# MCU099_02_XDS110_Debug_Probe.net
KiCad netlist of a schematic drawn in Altium Designer
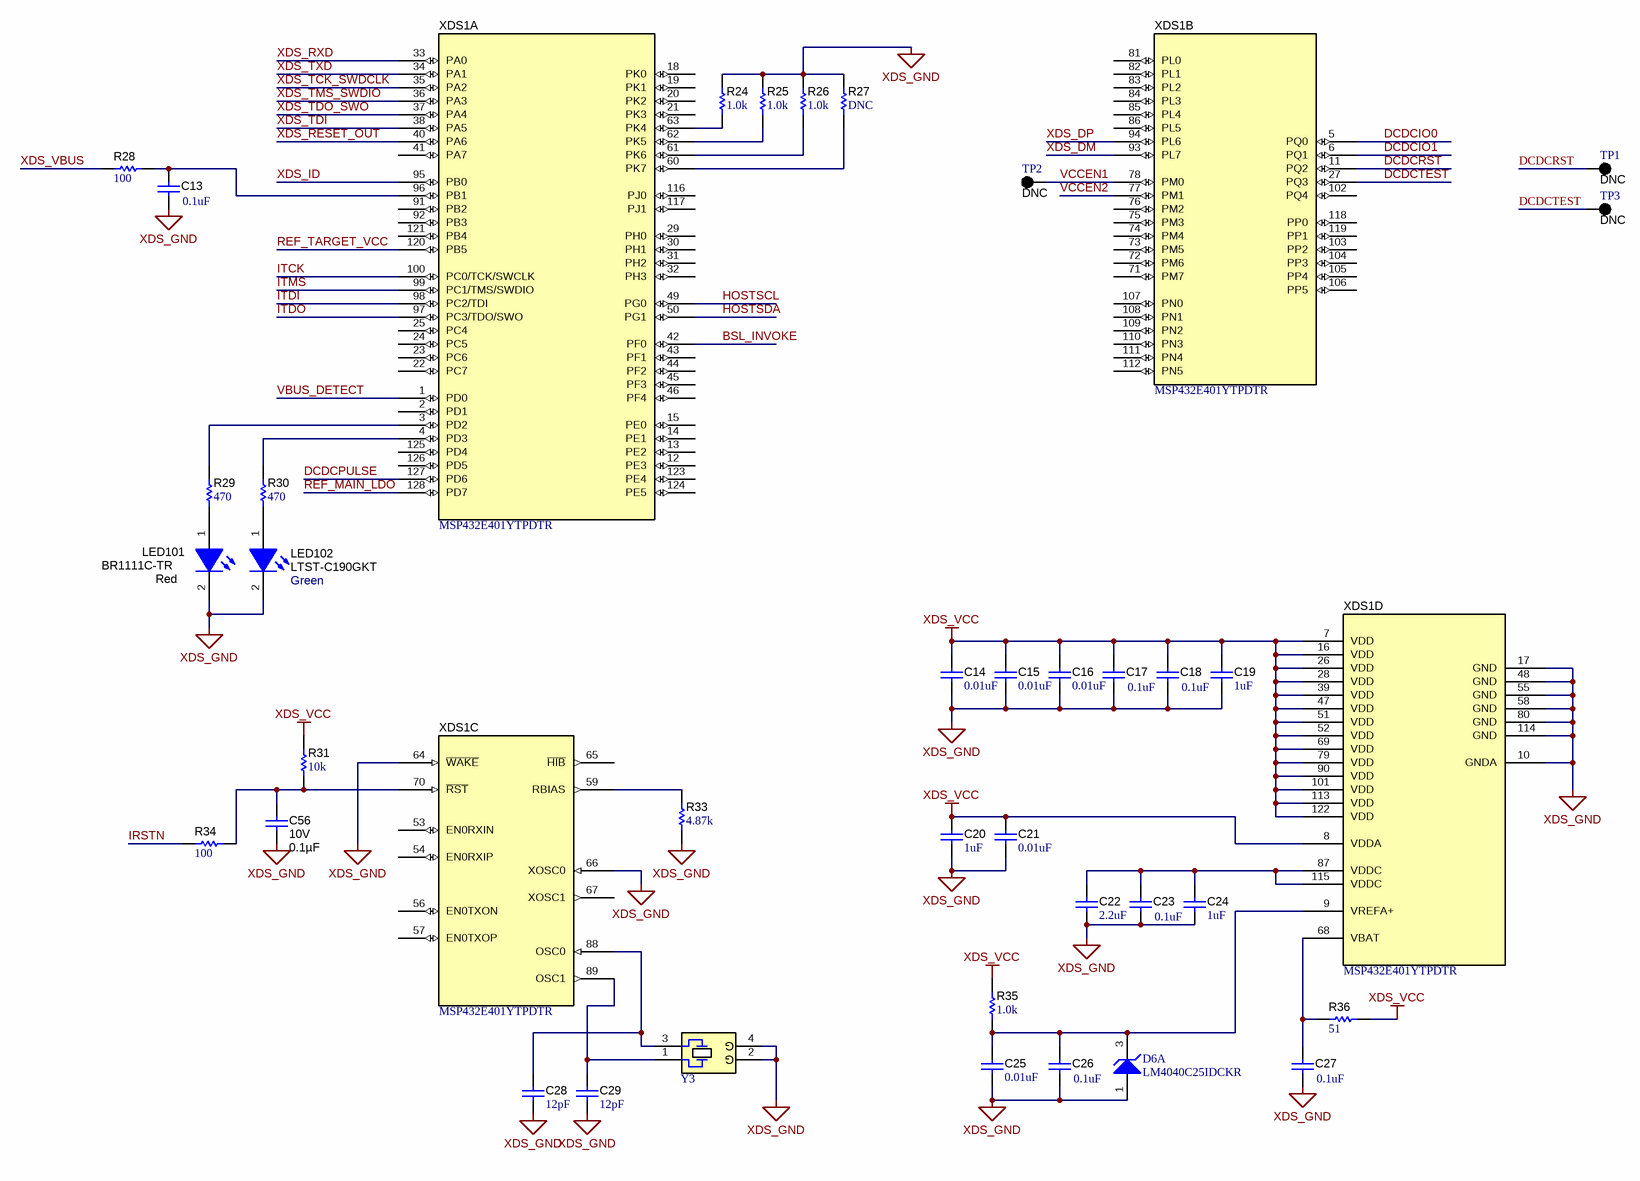
[diagram p0: MCU099_02_XDS110_Debug_Probe.SchDoc]

(export (version "E")
  (design (tool "Eeschema 10.0.6"))
  (components
    (comp (ref "C13")
      (value "C1005X5R1A104K050BA")
      (footprint "0402")
      (description "CAP, CERM, 0.1 uF, 10 V, +/- 10%, X5R, 0402")
      (fields
        (field (name "MANUFACTURER") "TDK")
        (field (name "VALUEDISPLAYED") "0.1uF")
        (field (name "PUBLISHER") "Texas Instruments")
      )
      (libsource (lib "Altium Vault - TI") (part "Capacitor"))
    )
    (comp (ref "C14")
      (value "GRM155R71E103KA01D")
      (footprint "0402")
      (description "CAP, CERM, 0.01 uF, 25 V, +/- 10%, X7R, 0402")
      (fields
        (field (name "MANUFACTURER") "MuRata")
        (field (name "VALUEDISPLAYED") "0.01uF")
        (field (name "PUBLISHER") "Texas Instruments")
      )
      (libsource (lib "Altium Vault - TI") (part "Capacitor"))
    )
    (comp (ref "C15")
      (value "GRM155R71E103KA01D")
      (footprint "0402")
      (description "CAP, CERM, 0.01 uF, 25 V, +/- 10%, X7R, 0402")
      (fields
        (field (name "MANUFACTURER") "MuRata")
        (field (name "VALUEDISPLAYED") "0.01uF")
        (field (name "PUBLISHER") "Texas Instruments")
      )
      (libsource (lib "Altium Vault - TI") (part "Capacitor"))
    )
    (comp (ref "C16")
      (value "GRM155R71E103KA01D")
      (footprint "0402")
      (description "CAP, CERM, 0.01 uF, 25 V, +/- 10%, X7R, 0402")
      (fields
        (field (name "MANUFACTURER") "MuRata")
        (field (name "VALUEDISPLAYED") "0.01uF")
        (field (name "PUBLISHER") "Texas Instruments")
      )
      (libsource (lib "Altium Vault - TI") (part "Capacitor"))
    )
    (comp (ref "C17")
      (value "C1005X5R1A104K050BA")
      (footprint "0402")
      (description "CAP, CERM, 0.1 uF, 10 V, +/- 10%, X5R, 0402")
      (fields
        (field (name "MANUFACTURER") "TDK")
        (field (name "VALUEDISPLAYED") "0.1uF")
        (field (name "PUBLISHER") "Texas Instruments")
      )
      (libsource (lib "Altium Vault - TI") (part "Capacitor"))
    )
    (comp (ref "C18")
      (value "C1005X5R1A104K050BA")
      (footprint "0402")
      (description "CAP, CERM, 0.1 uF, 10 V, +/- 10%, X5R, 0402")
      (fields
        (field (name "MANUFACTURER") "TDK")
        (field (name "VALUEDISPLAYED") "0.1uF")
        (field (name "PUBLISHER") "Texas Instruments")
      )
      (libsource (lib "Altium Vault - TI") (part "Capacitor"))
    )
    (comp (ref "C19")
      (value "C1005X5R1E105K050BC")
      (footprint "0402")
      (description "CAP, CERM, 1 uF, 25 V, +/- 10%, X5R, 0402")
      (fields
        (field (name "MANUFACTURER") "TDK")
        (field (name "VALUEDISPLAYED") "1uF")
        (field (name "PUBLISHER") "Texas Instruments")
      )
      (libsource (lib "Altium Vault - TI") (part "Capacitor"))
    )
    (comp (ref "C20")
      (value "C1005X5R1E105K050BC")
      (footprint "0402")
      (description "CAP, CERM, 1 uF, 25 V, +/- 10%, X5R, 0402")
      (fields
        (field (name "MANUFACTURER") "TDK")
        (field (name "VALUEDISPLAYED") "1uF")
        (field (name "PUBLISHER") "Texas Instruments")
      )
      (libsource (lib "Altium Vault - TI") (part "Capacitor"))
    )
    (comp (ref "C21")
      (value "GRM155R71E103KA01D")
      (footprint "0402")
      (description "CAP, CERM, 0.01 uF, 25 V, +/- 10%, X7R, 0402")
      (fields
        (field (name "MANUFACTURER") "MuRata")
        (field (name "VALUEDISPLAYED") "0.01uF")
        (field (name "PUBLISHER") "Texas Instruments")
      )
      (libsource (lib "Altium Vault - TI") (part "Capacitor"))
    )
    (comp (ref "C22")
      (value "GRM155R60J225KE95D")
      (footprint "0402")
      (description "CAP, CERM, 2.2 uF, 6.3 V, +/- 10%, X5R, 0402")
      (fields
        (field (name "MANUFACTURER") "MuRata")
        (field (name "VALUEDISPLAYED") "2.2uF")
        (field (name "PUBLISHER") "Texas Instruments")
      )
      (libsource (lib "Altium Vault - TI") (part "Capacitor"))
    )
    (comp (ref "C23")
      (value "C1005X5R1A104K050BA")
      (footprint "0402")
      (description "CAP, CERM, 0.1 uF, 10 V, +/- 10%, X5R, 0402")
      (fields
        (field (name "MANUFACTURER") "TDK")
        (field (name "VALUEDISPLAYED") "0.1uF")
        (field (name "PUBLISHER") "Texas Instruments")
      )
      (libsource (lib "Altium Vault - TI") (part "Capacitor"))
    )
    (comp (ref "C24")
      (value "C1005X5R1E105K050BC")
      (footprint "0402")
      (description "CAP, CERM, 1 uF, 25 V, +/- 10%, X5R, 0402")
      (fields
        (field (name "MANUFACTURER") "TDK")
        (field (name "VALUEDISPLAYED") "1uF")
        (field (name "PUBLISHER") "Texas Instruments")
      )
      (libsource (lib "Altium Vault - TI") (part "Capacitor"))
    )
    (comp (ref "C25")
      (value "GRM155R71E103KA01D")
      (footprint "0402")
      (description "CAP, CERM, 0.01 uF, 25 V, +/- 10%, X7R, 0402")
      (fields
        (field (name "MANUFACTURER") "MuRata")
        (field (name "VALUEDISPLAYED") "0.01uF")
        (field (name "PUBLISHER") "Texas Instruments")
      )
      (libsource (lib "Altium Vault - TI") (part "Capacitor"))
    )
    (comp (ref "C26")
      (value "C1005X5R1A104K050BA")
      (footprint "0402")
      (description "CAP, CERM, 0.1 uF, 10 V, +/- 10%, X5R, 0402")
      (fields
        (field (name "MANUFACTURER") "TDK")
        (field (name "VALUEDISPLAYED") "0.1uF")
        (field (name "PUBLISHER") "Texas Instruments")
      )
      (libsource (lib "Altium Vault - TI") (part "Capacitor"))
    )
    (comp (ref "C27")
      (value "C1005X5R1A104K050BA")
      (footprint "0402")
      (description "CAP, CERM, 0.1 uF, 10 V, +/- 10%, X5R, 0402")
      (fields
        (field (name "MANUFACTURER") "TDK")
        (field (name "VALUEDISPLAYED") "0.1uF")
        (field (name "PUBLISHER") "Texas Instruments")
      )
      (libsource (lib "Altium Vault - TI") (part "Capacitor"))
    )
    (comp (ref "C28")
      (value "GRM1555C1H120JA01D")
      (footprint "0402")
      (description "CAP, CERM, 12 pF, 50 V, +/- 5%, C0G/NP0, 0402")
      (fields
        (field (name "MANUFACTURER") "MuRata")
        (field (name "VALUEDISPLAYED") "12pF")
        (field (name "PUBLISHER") "Texas Instruments")
      )
      (libsource (lib "Altium Vault - TI") (part "Capacitor"))
    )
    (comp (ref "C29")
      (value "GRM1555C1H120JA01D")
      (footprint "0402")
      (description "CAP, CERM, 12 pF, 50 V, +/- 5%, C0G/NP0, 0402")
      (fields
        (field (name "MANUFACTURER") "MuRata")
        (field (name "VALUEDISPLAYED") "12pF")
        (field (name "PUBLISHER") "Texas Instruments")
      )
      (libsource (lib "Altium Vault - TI") (part "Capacitor"))
    )
    (comp (ref "C56")
      (value "C0402C104K8RACTU")
      (footprint "0402")
      (description "CAP, CERM, 0.1 µF, 10 V,+/- 10%, X7R, 0402")
      (fields
        (field (name "MANUFACTURER") "Kemet")
        (field (name "VDC_V") "10V")
        (field (name "VALUEDISPLAYED") "0.1µF")
      )
      (libsource (lib "Altium Vault - TI") (part "Capacitor"))
    )
    (comp (ref "D6")
      (value "LM4040B25IDCKR")
      (footprint "DCK0005A_N")
      (fields (field (name "MANUFACTURER") "Texas Instruments") (field (name "PARTNUMBER") "LM4040C25IDCKR"))
      (libsource (lib "Altium Vault - TI") (part "TI-LM4040B25DCK5"))
    )
    (comp (ref "LED101")
      (value "BR1111C-TR")
      (footprint "1111C_Red")
      (description "LED, Red, SMD")
      (fields (field (name "ALTIUM_VALUE") "Red") (field (name "MANUFACTURER") "Stanley Electric Co., LTD"))
      (libsource (lib "Altium Vault - TI") (part "LED"))
    )
    (comp (ref "LED102")
      (value "LTST-C190GKT")
      (footprint "LED_LTST-C190")
      (description "LED, Green, SMD")
      (fields (field (name "ALTIUM_VALUE") "Green") (field (name "MANUFACTURER") "Lite-On"))
      (libsource (lib "Altium Vault - TI") (part "LED"))
    )
    (comp (ref "R24")
      (value "CRCW04021K00JNED")
      (footprint "0402")
      (description "RES, 1.0 k, 5%, 0.063 W, 0402")
      (fields
        (field (name "MANUFACTURER") "Vishay-Dale")
        (field (name "VALUEDISPLAYED") "1.0k")
        (field (name "PUBLISHER") "Texas Instruments")
      )
      (libsource (lib "Altium Vault - TI") (part "Resistor"))
    )
    (comp (ref "R25")
      (value "CRCW04021K00JNED")
      (footprint "0402")
      (description "RES, 1.0 k, 5%, 0.063 W, 0402")
      (fields
        (field (name "MANUFACTURER") "Vishay-Dale")
        (field (name "VALUEDISPLAYED") "1.0k")
        (field (name "PUBLISHER") "Texas Instruments")
      )
      (libsource (lib "Altium Vault - TI") (part "Resistor"))
    )
    (comp (ref "R26")
      (value "CRCW04021K00JNED")
      (footprint "0402")
      (description "RES, 1.0 k, 5%, 0.063 W, 0402")
      (fields
        (field (name "MANUFACTURER") "Vishay-Dale")
        (field (name "VALUEDISPLAYED") "1.0k")
        (field (name "PUBLISHER") "Texas Instruments")
      )
      (libsource (lib "Altium Vault - TI") (part "Resistor"))
    )
    (comp (ref "R27")
      (value "CRCW04021K00JNED")
      (footprint "0402")
      (description "RES, 1.0 k, 5%, 0.063 W, 0402")
      (fields
        (field (name "MANUFACTURER") "Vishay-Dale")
        (field (name "VALUEDISPLAYED") "DNC")
        (field (name "PUBLISHER") "Texas Instruments")
      )
      (libsource (lib "Altium Vault - TI") (part "Resistor"))
    )
    (comp (ref "R28")
      (value "CRCW0402100RJNED")
      (footprint "0402")
      (description "RES, 100, 5%, 0.063 W, AEC-Q200 Grade 0, 0402")
      (fields (field (name "MANUFACTURER") "Vishay-Dale") (field (name "VALUEDISPLAYED") "100"))
      (libsource (lib "Altium Vault - TI") (part "Resistor"))
    )
    (comp (ref "R29")
      (value "CRCW0402470RJNED")
      (footprint "0402")
      (description "RES, 470, 5%, 0.063 W, 0402")
      (fields
        (field (name "MANUFACTURER") "Vishay-Dale")
        (field (name "VALUEDISPLAYED") "470")
        (field (name "PUBLISHER") "Texas Instruments")
      )
      (libsource (lib "Altium Vault - TI") (part "Resistor"))
    )
    (comp (ref "R30")
      (value "CRCW0402470RJNED")
      (footprint "0402")
      (description "RES, 470, 5%, 0.063 W, 0402")
      (fields
        (field (name "MANUFACTURER") "Vishay-Dale")
        (field (name "VALUEDISPLAYED") "470")
        (field (name "PUBLISHER") "Texas Instruments")
      )
      (libsource (lib "Altium Vault - TI") (part "Resistor"))
    )
    (comp (ref "R31")
      (value "CRCW040210K0JNED")
      (footprint "0402")
      (description "RES, 10 k, 5%, 0.063 W, 0402")
      (fields
        (field (name "MANUFACTURER") "Vishay-Dale")
        (field (name "VALUEDISPLAYED") "10k")
        (field (name "PUBLISHER") "Texas Instruments")
      )
      (libsource (lib "Altium Vault - TI") (part "Resistor"))
    )
    (comp (ref "R33")
      (value "CRCW04024K87FKED")
      (footprint "0402")
      (description "RES, 4.87 k, 1%, 0.063 W, AEC-Q200 Grade 0, 0402")
      (fields (field (name "MANUFACTURER") "Vishay-Dale") (field (name "VALUEDISPLAYED") "4.87k"))
      (libsource (lib "Altium Vault - TI") (part "Resistor"))
    )
    (comp (ref "R34")
      (value "CRCW0402100RJNED")
      (footprint "0402")
      (description "RES, 100, 5%, 0.063 W, 0402")
      (fields
        (field (name "MANUFACTURER") "Vishay-Dale")
        (field (name "VALUEDISPLAYED") "100")
        (field (name "PUBLISHER") "Texas Instruments")
      )
      (libsource (lib "Altium Vault - TI") (part "Resistor"))
    )
    (comp (ref "R35")
      (value "CRCW04021K00JNED")
      (footprint "0402")
      (description "RES, 1.0 k, 5%, 0.063 W, 0402")
      (fields
        (field (name "MANUFACTURER") "Vishay-Dale")
        (field (name "VALUEDISPLAYED") "1.0k")
        (field (name "PUBLISHER") "Texas Instruments")
      )
      (libsource (lib "Altium Vault - TI") (part "Resistor"))
    )
    (comp (ref "R36")
      (value "CRCW040251R0JNED")
      (footprint "0402")
      (description "RES, 51, 5%, 0.063 W, AEC-Q200 Grade 0, 0402")
      (fields (field (name "MANUFACTURER") "Vishay-Dale") (field (name "VALUEDISPLAYED") "51"))
      (libsource (lib "Altium Vault - TI") (part "Resistor"))
    )
    (comp (ref "TP1")
      (value "DNC")
      (footprint "Keystone5001")
      (description "Test Point, Miniature, Black, TH")
      (fields
        (field (name "MANUFACTURER") "Keystone")
        (field (name "PARTNUMBER") "5001")
        (field (name "PUBLISHER") "Texas Instruments")
      )
      (libsource (lib "Altium Vault - TI") (part "5001"))
    )
    (comp (ref "TP2")
      (value "DNC")
      (footprint "Keystone5001")
      (description "Test Point, Miniature, Black, TH")
      (fields
        (field (name "MANUFACTURER") "Keystone")
        (field (name "PARTNUMBER") "5001")
        (field (name "PUBLISHER") "Texas Instruments")
      )
      (libsource (lib "Altium Vault - TI") (part "5001"))
    )
    (comp (ref "TP3")
      (value "DNC")
      (footprint "Keystone5001")
      (description "Test Point, Miniature, Black, TH")
      (fields
        (field (name "MANUFACTURER") "Keystone")
        (field (name "PARTNUMBER") "5001")
        (field (name "PUBLISHER") "Texas Instruments")
      )
      (libsource (lib "Altium Vault - TI") (part "5001"))
    )
    (comp (ref "XDS1")
      (value "MSP432E401YTPDTR")
      (footprint "PDT0128A")
      (description "MSP432E401YTPDT, PDT0128A (TQFP-128)")
      (fields
        (field (name "ALTERNATE PARTNUMBER") "MSP432E401YTPDT")
        (field (name "MANUFACTURER") "Texas Instruments")
        (field (name "PARTNUMBER") "MSP432E401YTPDTR")
      )
      (libsource (lib "Altium Vault - TI") (part "MSP432E401YTPDT"))
    )
    (comp (ref "Y3")
      (value "NX3225GA-16.000M-STD-CRG-1")
      (footprint "NDK_NX3225GA")
      (description "Crystal, 16 MHz, 8pF, SMD")
      (fields (field (name "MANUFACTURER") "NDK") (field (name "PUBLISHER") "Texas Instruments"))
      (libsource (lib "Altium Vault - TI") (part "XTAL_4P_13_G24"))
    )
  )
  (nets
    (net (code "1") (name "/BSL_INVOKE") (class "Default")
      (node (ref "XDS1") (pin "42") (pinfunction "PF0_42") (pintype "bidirectional"))
    )
    (net (code "2") (name "/DCDCIO0") (class "Default")
      (node (ref "XDS1") (pin "5") (pinfunction "PQ0_5") (pintype "bidirectional"))
    )
    (net (code "3") (name "/DCDCIO1") (class "Default")
      (node (ref "XDS1") (pin "6") (pinfunction "PQ1_6") (pintype "bidirectional"))
    )
    (net (code "4") (name "/DCDCPULSE") (class "Default")
      (node (ref "XDS1") (pin "127") (pinfunction "PD6_127") (pintype "bidirectional"))
    )
    (net (code "5") (name "/DCDCRST") (class "Default")
      (node (ref "TP1") (pin "1") (pintype "passive"))
      (node (ref "XDS1") (pin "11") (pinfunction "PQ2_11") (pintype "bidirectional"))
    )
    (net (code "6") (name "/DCDCTEST") (class "Default")
      (node (ref "TP3") (pin "1") (pintype "passive"))
      (node (ref "XDS1") (pin "27") (pinfunction "PQ3_27") (pintype "bidirectional"))
    )
    (net (code "7") (name "/HOSTSCL") (class "Default")
      (node (ref "XDS1") (pin "49") (pinfunction "PG0_49") (pintype "bidirectional"))
    )
    (net (code "8") (name "/HOSTSDA") (class "Default")
      (node (ref "XDS1") (pin "50") (pinfunction "PG1_50") (pintype "bidirectional"))
    )
    (net (code "9") (name "/IRSTN") (class "Default")
      (node (ref "R34") (pin "1") (pinfunction "1_1") (pintype "passive"))
    )
    (net (code "10") (name "/ITCK") (class "Default")
      (node (ref "XDS1") (pin "100") (pinfunction "PC0/TCK/SWCLK_100") (pintype "bidirectional"))
    )
    (net (code "11") (name "/ITDI") (class "Default")
      (node (ref "XDS1") (pin "98") (pinfunction "PC2/TDI_98") (pintype "bidirectional"))
    )
    (net (code "12") (name "/ITDO") (class "Default")
      (node (ref "XDS1") (pin "97") (pinfunction "PC3/TDO/SWO_97") (pintype "bidirectional"))
    )
    (net (code "13") (name "/ITMS") (class "Default")
      (node (ref "XDS1") (pin "99") (pinfunction "PC1/TMS/SWDIO_99") (pintype "bidirectional"))
    )
    (net (code "14") (name "/REF_MAIN_LDO") (class "Default")
      (node (ref "XDS1") (pin "128") (pinfunction "PD7_128") (pintype "bidirectional"))
    )
    (net (code "15") (name "/REF_TARGET_VCC") (class "Default")
      (node (ref "XDS1") (pin "120") (pinfunction "PB5_120") (pintype "bidirectional"))
    )
    (net (code "16") (name "/VBUS_DETECT") (class "Default")
      (node (ref "XDS1") (pin "1") (pinfunction "PD0_1") (pintype "bidirectional"))
    )
    (net (code "17") (name "/VCCEN1") (class "Default")
      (node (ref "TP2") (pin "1") (pintype "passive"))
      (node (ref "XDS1") (pin "78") (pinfunction "PM0_78") (pintype "bidirectional"))
    )
    (net (code "18") (name "/VCCEN2") (class "Default")
      (node (ref "XDS1") (pin "77") (pinfunction "PM1_77") (pintype "bidirectional"))
    )
    (net (code "19") (name "/XDS_DM") (class "Default")
      (node (ref "XDS1") (pin "93") (pinfunction "PL7_93") (pintype "bidirectional"))
    )
    (net (code "20") (name "/XDS_DP") (class "Default")
      (node (ref "XDS1") (pin "94") (pinfunction "PL6_94") (pintype "bidirectional"))
    )
    (net (code "21") (name "/XDS_ID") (class "Default")
      (node (ref "XDS1") (pin "95") (pinfunction "PB0_95") (pintype "bidirectional"))
    )
    (net (code "22") (name "/XDS_RESET_OUT") (class "Default")
      (node (ref "XDS1") (pin "40") (pinfunction "PA6_40") (pintype "bidirectional"))
    )
    (net (code "23") (name "/XDS_RXD") (class "Default")
      (node (ref "XDS1") (pin "33") (pinfunction "PA0_33") (pintype "bidirectional"))
    )
    (net (code "24") (name "/XDS_TCK_SWDCLK") (class "Default")
      (node (ref "XDS1") (pin "35") (pinfunction "PA2_35") (pintype "bidirectional"))
    )
    (net (code "25") (name "/XDS_TDI") (class "Default")
      (node (ref "XDS1") (pin "38") (pinfunction "PA5_38") (pintype "bidirectional"))
    )
    (net (code "26") (name "/XDS_TDO_SWO") (class "Default")
      (node (ref "XDS1") (pin "37") (pinfunction "PA4_37") (pintype "bidirectional"))
    )
    (net (code "27") (name "/XDS_TMS_SWDIO") (class "Default")
      (node (ref "XDS1") (pin "36") (pinfunction "PA3_36") (pintype "bidirectional"))
    )
    (net (code "28") (name "/XDS_TXD") (class "Default")
      (node (ref "XDS1") (pin "34") (pinfunction "PA1_34") (pintype "bidirectional"))
    )
    (net (code "29") (name "/XDS_VBUS") (class "Default")
      (node (ref "R28") (pin "1") (pinfunction "1_1") (pintype "passive"))
    )
    (net (code "30") (name "Net-(C22-Pad1)") (class "Default")
      (node (ref "C22") (pin "1") (pinfunction "1_1") (pintype "passive"))
      (node (ref "C23") (pin "1") (pinfunction "1_1") (pintype "passive"))
      (node (ref "C24") (pin "1") (pinfunction "1_1") (pintype "passive"))
      (node (ref "XDS1") (pin "115") (pinfunction "VDDC_115") (pintype "power_in"))
      (node (ref "XDS1") (pin "87") (pinfunction "VDDC_87") (pintype "power_in"))
    )
    (net (code "31") (name "Net-(D6A-CATHODE)") (class "Default")
      (node (ref "C25") (pin "1") (pinfunction "1_1") (pintype "passive"))
      (node (ref "C26") (pin "1") (pinfunction "1_1") (pintype "passive"))
      (node (ref "D6") (pin "3") (pinfunction "CATHODE_3") (pintype "passive"))
      (node (ref "R35") (pin "1") (pinfunction "1_1") (pintype "passive"))
      (node (ref "XDS1") (pin "9") (pinfunction "VREFA+_9") (pintype "power_in"))
    )
    (net (code "32") (name "Net-(LED101-A)") (class "Default")
      (node (ref "LED101") (pin "1") (pinfunction "A_1") (pintype "passive"))
      (node (ref "R29") (pin "1") (pinfunction "1_1") (pintype "passive"))
    )
    (net (code "33") (name "Net-(LED102-A)") (class "Default")
      (node (ref "LED102") (pin "1") (pinfunction "A_1") (pintype "passive"))
      (node (ref "R30") (pin "1") (pinfunction "1_1") (pintype "passive"))
    )
    (net (code "34") (name "Net-(XDS1A-PB1)") (class "Default")
      (node (ref "C13") (pin "1") (pinfunction "1_1") (pintype "passive"))
      (node (ref "R28") (pin "2") (pinfunction "2_2") (pintype "passive"))
      (node (ref "XDS1") (pin "96") (pinfunction "PB1_96") (pintype "bidirectional"))
    )
    (net (code "35") (name "Net-(XDS1A-PD2)") (class "Default")
      (node (ref "R29") (pin "2") (pinfunction "2_2") (pintype "passive"))
      (node (ref "XDS1") (pin "3") (pinfunction "PD2_3") (pintype "bidirectional"))
    )
    (net (code "36") (name "Net-(XDS1A-PD3)") (class "Default")
      (node (ref "R30") (pin "2") (pinfunction "2_2") (pintype "passive"))
      (node (ref "XDS1") (pin "4") (pinfunction "PD3_4") (pintype "bidirectional"))
    )
    (net (code "37") (name "Net-(XDS1A-PK4)") (class "Default")
      (node (ref "R24") (pin "1") (pinfunction "1_1") (pintype "passive"))
      (node (ref "XDS1") (pin "63") (pinfunction "PK4_63") (pintype "bidirectional"))
    )
    (net (code "38") (name "Net-(XDS1A-PK5)") (class "Default")
      (node (ref "R25") (pin "1") (pinfunction "1_1") (pintype "passive"))
      (node (ref "XDS1") (pin "62") (pinfunction "PK5_62") (pintype "bidirectional"))
    )
    (net (code "39") (name "Net-(XDS1A-PK6)") (class "Default")
      (node (ref "R26") (pin "1") (pinfunction "1_1") (pintype "passive"))
      (node (ref "XDS1") (pin "61") (pinfunction "PK6_61") (pintype "bidirectional"))
    )
    (net (code "40") (name "Net-(XDS1A-PK7)") (class "Default")
      (node (ref "R27") (pin "1") (pinfunction "1_1") (pintype "passive"))
      (node (ref "XDS1") (pin "60") (pinfunction "PK7_60") (pintype "bidirectional"))
    )
    (net (code "41") (name "Net-(XDS1C-OSC0)") (class "Default")
      (node (ref "C28") (pin "1") (pinfunction "1_1") (pintype "passive"))
      (node (ref "XDS1") (pin "88") (pinfunction "OSC0_88") (pintype "input"))
      (node (ref "Y3") (pin "3") (pinfunction "3_3") (pintype "passive"))
    )
    (net (code "42") (name "Net-(XDS1C-OSC1)") (class "Default")
      (node (ref "C29") (pin "1") (pinfunction "1_1") (pintype "passive"))
      (node (ref "XDS1") (pin "89") (pinfunction "OSC1_89") (pintype "output"))
      (node (ref "Y3") (pin "1") (pinfunction "1_1") (pintype "passive"))
    )
    (net (code "43") (name "Net-(XDS1C-RBIAS)") (class "Default")
      (node (ref "R33") (pin "2") (pinfunction "2_2") (pintype "passive"))
      (node (ref "XDS1") (pin "59") (pinfunction "RBIAS_59") (pintype "output"))
    )
    (net (code "44") (name "Net-(XDS1C-RST)") (class "Default")
      (node (ref "C56") (pin "1") (pinfunction "1_1") (pintype "passive"))
      (node (ref "R31") (pin "1") (pinfunction "1_1") (pintype "passive"))
      (node (ref "R34") (pin "2") (pinfunction "2_2") (pintype "passive"))
      (node (ref "XDS1") (pin "70") (pinfunction "RST_70") (pintype "input"))
    )
    (net (code "45") (name "Net-(XDS1D-VBAT)") (class "Default")
      (node (ref "C27") (pin "1") (pinfunction "1_1") (pintype "passive"))
      (node (ref "R36") (pin "1") (pinfunction "1_1") (pintype "passive"))
      (node (ref "XDS1") (pin "68") (pinfunction "VBAT_68") (pintype "power_in"))
    )
    (net (code "46") (name "XDS_GND") (class "Default")
      (node (ref "C13") (pin "2") (pinfunction "2_2") (pintype "passive"))
      (node (ref "C14") (pin "2") (pinfunction "2_2") (pintype "passive"))
      (node (ref "C15") (pin "2") (pinfunction "2_2") (pintype "passive"))
      (node (ref "C16") (pin "2") (pinfunction "2_2") (pintype "passive"))
      (node (ref "C17") (pin "2") (pinfunction "2_2") (pintype "passive"))
      (node (ref "C18") (pin "2") (pinfunction "2_2") (pintype "passive"))
      (node (ref "C19") (pin "2") (pinfunction "2_2") (pintype "passive"))
      (node (ref "C20") (pin "2") (pinfunction "2_2") (pintype "passive"))
      (node (ref "C21") (pin "2") (pinfunction "2_2") (pintype "passive"))
      (node (ref "C22") (pin "2") (pinfunction "2_2") (pintype "passive"))
      (node (ref "C23") (pin "2") (pinfunction "2_2") (pintype "passive"))
      (node (ref "C24") (pin "2") (pinfunction "2_2") (pintype "passive"))
      (node (ref "C25") (pin "2") (pinfunction "2_2") (pintype "passive"))
      (node (ref "C26") (pin "2") (pinfunction "2_2") (pintype "passive"))
      (node (ref "C27") (pin "2") (pinfunction "2_2") (pintype "passive"))
      (node (ref "C28") (pin "2") (pinfunction "2_2") (pintype "passive"))
      (node (ref "C29") (pin "2") (pinfunction "2_2") (pintype "passive"))
      (node (ref "C56") (pin "2") (pinfunction "2_2") (pintype "passive"))
      (node (ref "D6") (pin "1") (pinfunction "ANODE_1") (pintype "passive"))
      (node (ref "LED101") (pin "2") (pinfunction "K_2") (pintype "passive"))
      (node (ref "LED102") (pin "2") (pinfunction "K_2") (pintype "passive"))
      (node (ref "R24") (pin "2") (pinfunction "2_2") (pintype "passive"))
      (node (ref "R25") (pin "2") (pinfunction "2_2") (pintype "passive"))
      (node (ref "R26") (pin "2") (pinfunction "2_2") (pintype "passive"))
      (node (ref "R27") (pin "2") (pinfunction "2_2") (pintype "passive"))
      (node (ref "R33") (pin "1") (pinfunction "1_1") (pintype "passive"))
      (node (ref "XDS1") (pin "10") (pinfunction "GNDA_10") (pintype "power_in"))
      (node (ref "XDS1") (pin "114") (pinfunction "GND_114") (pintype "power_in"))
      (node (ref "XDS1") (pin "17") (pinfunction "GND_17") (pintype "power_in"))
      (node (ref "XDS1") (pin "48") (pinfunction "GND_48") (pintype "power_in"))
      (node (ref "XDS1") (pin "55") (pinfunction "GND_55") (pintype "power_in"))
      (node (ref "XDS1") (pin "58") (pinfunction "GND_58") (pintype "power_in"))
      (node (ref "XDS1") (pin "64") (pinfunction "WAKE_64") (pintype "input"))
      (node (ref "XDS1") (pin "66") (pinfunction "XOSC0_66") (pintype "input"))
      (node (ref "XDS1") (pin "80") (pinfunction "GND_80") (pintype "power_in"))
      (node (ref "Y3") (pin "2") (pinfunction "GND_2") (pintype "power_in"))
      (node (ref "Y3") (pin "4") (pinfunction "GND_4") (pintype "power_in"))
    )
    (net (code "47") (name "XDS_VCC") (class "Default")
      (node (ref "C14") (pin "1") (pinfunction "1_1") (pintype "passive"))
      (node (ref "C15") (pin "1") (pinfunction "1_1") (pintype "passive"))
      (node (ref "C16") (pin "1") (pinfunction "1_1") (pintype "passive"))
      (node (ref "C17") (pin "1") (pinfunction "1_1") (pintype "passive"))
      (node (ref "C18") (pin "1") (pinfunction "1_1") (pintype "passive"))
      (node (ref "C19") (pin "1") (pinfunction "1_1") (pintype "passive"))
      (node (ref "C20") (pin "1") (pinfunction "1_1") (pintype "passive"))
      (node (ref "C21") (pin "1") (pinfunction "1_1") (pintype "passive"))
      (node (ref "R31") (pin "2") (pinfunction "2_2") (pintype "passive"))
      (node (ref "R35") (pin "2") (pinfunction "2_2") (pintype "passive"))
      (node (ref "R36") (pin "2") (pinfunction "2_2") (pintype "passive"))
      (node (ref "XDS1") (pin "101") (pinfunction "VDD_101") (pintype "power_in"))
      (node (ref "XDS1") (pin "113") (pinfunction "VDD_113") (pintype "power_in"))
      (node (ref "XDS1") (pin "122") (pinfunction "VDD_122") (pintype "power_in"))
      (node (ref "XDS1") (pin "16") (pinfunction "VDD_16") (pintype "power_in"))
      (node (ref "XDS1") (pin "26") (pinfunction "VDD_26") (pintype "power_in"))
      (node (ref "XDS1") (pin "28") (pinfunction "VDD_28") (pintype "power_in"))
      (node (ref "XDS1") (pin "39") (pinfunction "VDD_39") (pintype "power_in"))
      (node (ref "XDS1") (pin "47") (pinfunction "VDD_47") (pintype "power_in"))
      (node (ref "XDS1") (pin "51") (pinfunction "VDD_51") (pintype "power_in"))
      (node (ref "XDS1") (pin "52") (pinfunction "VDD_52") (pintype "power_in"))
      (node (ref "XDS1") (pin "69") (pinfunction "VDD_69") (pintype "power_in"))
      (node (ref "XDS1") (pin "7") (pinfunction "VDD_7") (pintype "power_in"))
      (node (ref "XDS1") (pin "79") (pinfunction "VDD_79") (pintype "power_in"))
      (node (ref "XDS1") (pin "8") (pinfunction "VDDA_8") (pintype "power_in"))
      (node (ref "XDS1") (pin "90") (pinfunction "VDD_90") (pintype "power_in"))
    )
    (net (code "48") (name "unconnected-(XDS1A-PA7-Pad41)") (class "Default")
      (node (ref "XDS1") (pin "41") (pinfunction "PA7_41") (pintype "bidirectional"))
    )
    (net (code "49") (name "unconnected-(XDS1A-PB2-Pad91)") (class "Default")
      (node (ref "XDS1") (pin "91") (pinfunction "PB2_91") (pintype "bidirectional"))
    )
    (net (code "50") (name "unconnected-(XDS1A-PB3-Pad92)") (class "Default")
      (node (ref "XDS1") (pin "92") (pinfunction "PB3_92") (pintype "bidirectional"))
    )
    (net (code "51") (name "unconnected-(XDS1A-PB4-Pad121)") (class "Default")
      (node (ref "XDS1") (pin "121") (pinfunction "PB4_121") (pintype "bidirectional"))
    )
    (net (code "52") (name "unconnected-(XDS1A-PC4-Pad25)") (class "Default")
      (node (ref "XDS1") (pin "25") (pinfunction "PC4_25") (pintype "bidirectional"))
    )
    (net (code "53") (name "unconnected-(XDS1A-PC5-Pad24)") (class "Default")
      (node (ref "XDS1") (pin "24") (pinfunction "PC5_24") (pintype "bidirectional"))
    )
    (net (code "54") (name "unconnected-(XDS1A-PC6-Pad23)") (class "Default")
      (node (ref "XDS1") (pin "23") (pinfunction "PC6_23") (pintype "bidirectional"))
    )
    (net (code "55") (name "unconnected-(XDS1A-PC7-Pad22)") (class "Default")
      (node (ref "XDS1") (pin "22") (pinfunction "PC7_22") (pintype "bidirectional"))
    )
    (net (code "56") (name "unconnected-(XDS1A-PD1-Pad2)") (class "Default")
      (node (ref "XDS1") (pin "2") (pinfunction "PD1_2") (pintype "bidirectional"))
    )
    (net (code "57") (name "unconnected-(XDS1A-PD4-Pad125)") (class "Default")
      (node (ref "XDS1") (pin "125") (pinfunction "PD4_125") (pintype "bidirectional"))
    )
    (net (code "58") (name "unconnected-(XDS1A-PD5-Pad126)") (class "Default")
      (node (ref "XDS1") (pin "126") (pinfunction "PD5_126") (pintype "bidirectional"))
    )
    (net (code "59") (name "unconnected-(XDS1A-PE0-Pad15)") (class "Default")
      (node (ref "XDS1") (pin "15") (pinfunction "PE0_15") (pintype "bidirectional"))
    )
    (net (code "60") (name "unconnected-(XDS1A-PE1-Pad14)") (class "Default")
      (node (ref "XDS1") (pin "14") (pinfunction "PE1_14") (pintype "bidirectional"))
    )
    (net (code "61") (name "unconnected-(XDS1A-PE2-Pad13)") (class "Default")
      (node (ref "XDS1") (pin "13") (pinfunction "PE2_13") (pintype "bidirectional"))
    )
    (net (code "62") (name "unconnected-(XDS1A-PE3-Pad12)") (class "Default")
      (node (ref "XDS1") (pin "12") (pinfunction "PE3_12") (pintype "bidirectional"))
    )
    (net (code "63") (name "unconnected-(XDS1A-PE4-Pad123)") (class "Default")
      (node (ref "XDS1") (pin "123") (pinfunction "PE4_123") (pintype "bidirectional"))
    )
    (net (code "64") (name "unconnected-(XDS1A-PE5-Pad124)") (class "Default")
      (node (ref "XDS1") (pin "124") (pinfunction "PE5_124") (pintype "bidirectional"))
    )
    (net (code "65") (name "unconnected-(XDS1A-PF1-Pad43)") (class "Default")
      (node (ref "XDS1") (pin "43") (pinfunction "PF1_43") (pintype "bidirectional"))
    )
    (net (code "66") (name "unconnected-(XDS1A-PF2-Pad44)") (class "Default")
      (node (ref "XDS1") (pin "44") (pinfunction "PF2_44") (pintype "bidirectional"))
    )
    (net (code "67") (name "unconnected-(XDS1A-PF3-Pad45)") (class "Default")
      (node (ref "XDS1") (pin "45") (pinfunction "PF3_45") (pintype "bidirectional"))
    )
    (net (code "68") (name "unconnected-(XDS1A-PF4-Pad46)") (class "Default")
      (node (ref "XDS1") (pin "46") (pinfunction "PF4_46") (pintype "bidirectional"))
    )
    (net (code "69") (name "unconnected-(XDS1A-PH0-Pad29)") (class "Default")
      (node (ref "XDS1") (pin "29") (pinfunction "PH0_29") (pintype "bidirectional"))
    )
    (net (code "70") (name "unconnected-(XDS1A-PH1-Pad30)") (class "Default")
      (node (ref "XDS1") (pin "30") (pinfunction "PH1_30") (pintype "bidirectional"))
    )
    (net (code "71") (name "unconnected-(XDS1A-PH2-Pad31)") (class "Default")
      (node (ref "XDS1") (pin "31") (pinfunction "PH2_31") (pintype "bidirectional"))
    )
    (net (code "72") (name "unconnected-(XDS1A-PH3-Pad32)") (class "Default")
      (node (ref "XDS1") (pin "32") (pinfunction "PH3_32") (pintype "bidirectional"))
    )
    (net (code "73") (name "unconnected-(XDS1A-PJ0-Pad116)") (class "Default")
      (node (ref "XDS1") (pin "116") (pinfunction "PJ0_116") (pintype "bidirectional"))
    )
    (net (code "74") (name "unconnected-(XDS1A-PJ1-Pad117)") (class "Default")
      (node (ref "XDS1") (pin "117") (pinfunction "PJ1_117") (pintype "bidirectional"))
    )
    (net (code "75") (name "unconnected-(XDS1A-PK0-Pad18)") (class "Default")
      (node (ref "XDS1") (pin "18") (pinfunction "PK0_18") (pintype "bidirectional"))
    )
    (net (code "76") (name "unconnected-(XDS1A-PK1-Pad19)") (class "Default")
      (node (ref "XDS1") (pin "19") (pinfunction "PK1_19") (pintype "bidirectional"))
    )
    (net (code "77") (name "unconnected-(XDS1A-PK2-Pad20)") (class "Default")
      (node (ref "XDS1") (pin "20") (pinfunction "PK2_20") (pintype "bidirectional"))
    )
    (net (code "78") (name "unconnected-(XDS1A-PK3-Pad21)") (class "Default")
      (node (ref "XDS1") (pin "21") (pinfunction "PK3_21") (pintype "bidirectional"))
    )
    (net (code "79") (name "unconnected-(XDS1B-PL0-Pad81)") (class "Default")
      (node (ref "XDS1") (pin "81") (pinfunction "PL0_81") (pintype "bidirectional"))
    )
    (net (code "80") (name "unconnected-(XDS1B-PL1-Pad82)") (class "Default")
      (node (ref "XDS1") (pin "82") (pinfunction "PL1_82") (pintype "bidirectional"))
    )
    (net (code "81") (name "unconnected-(XDS1B-PL2-Pad83)") (class "Default")
      (node (ref "XDS1") (pin "83") (pinfunction "PL2_83") (pintype "bidirectional"))
    )
    (net (code "82") (name "unconnected-(XDS1B-PL3-Pad84)") (class "Default")
      (node (ref "XDS1") (pin "84") (pinfunction "PL3_84") (pintype "bidirectional"))
    )
    (net (code "83") (name "unconnected-(XDS1B-PL4-Pad85)") (class "Default")
      (node (ref "XDS1") (pin "85") (pinfunction "PL4_85") (pintype "bidirectional"))
    )
    (net (code "84") (name "unconnected-(XDS1B-PL5-Pad86)") (class "Default")
      (node (ref "XDS1") (pin "86") (pinfunction "PL5_86") (pintype "bidirectional"))
    )
    (net (code "85") (name "unconnected-(XDS1B-PM2-Pad76)") (class "Default")
      (node (ref "XDS1") (pin "76") (pinfunction "PM2_76") (pintype "bidirectional"))
    )
    (net (code "86") (name "unconnected-(XDS1B-PM3-Pad75)") (class "Default")
      (node (ref "XDS1") (pin "75") (pinfunction "PM3_75") (pintype "bidirectional"))
    )
    (net (code "87") (name "unconnected-(XDS1B-PM4-Pad74)") (class "Default")
      (node (ref "XDS1") (pin "74") (pinfunction "PM4_74") (pintype "bidirectional"))
    )
    (net (code "88") (name "unconnected-(XDS1B-PM5-Pad73)") (class "Default")
      (node (ref "XDS1") (pin "73") (pinfunction "PM5_73") (pintype "bidirectional"))
    )
    (net (code "89") (name "unconnected-(XDS1B-PM6-Pad72)") (class "Default")
      (node (ref "XDS1") (pin "72") (pinfunction "PM6_72") (pintype "bidirectional"))
    )
    (net (code "90") (name "unconnected-(XDS1B-PM7-Pad71)") (class "Default")
      (node (ref "XDS1") (pin "71") (pinfunction "PM7_71") (pintype "bidirectional"))
    )
    (net (code "91") (name "unconnected-(XDS1B-PN0-Pad107)") (class "Default")
      (node (ref "XDS1") (pin "107") (pinfunction "PN0_107") (pintype "bidirectional"))
    )
    (net (code "92") (name "unconnected-(XDS1B-PN1-Pad108)") (class "Default")
      (node (ref "XDS1") (pin "108") (pinfunction "PN1_108") (pintype "bidirectional"))
    )
    (net (code "93") (name "unconnected-(XDS1B-PN2-Pad109)") (class "Default")
      (node (ref "XDS1") (pin "109") (pinfunction "PN2_109") (pintype "bidirectional"))
    )
    (net (code "94") (name "unconnected-(XDS1B-PN3-Pad110)") (class "Default")
      (node (ref "XDS1") (pin "110") (pinfunction "PN3_110") (pintype "bidirectional"))
    )
    (net (code "95") (name "unconnected-(XDS1B-PN4-Pad111)") (class "Default")
      (node (ref "XDS1") (pin "111") (pinfunction "PN4_111") (pintype "bidirectional"))
    )
    (net (code "96") (name "unconnected-(XDS1B-PN5-Pad112)") (class "Default")
      (node (ref "XDS1") (pin "112") (pinfunction "PN5_112") (pintype "bidirectional"))
    )
    (net (code "97") (name "unconnected-(XDS1B-PP0-Pad118)") (class "Default")
      (node (ref "XDS1") (pin "118") (pinfunction "PP0_118") (pintype "bidirectional"))
    )
    (net (code "98") (name "unconnected-(XDS1B-PP1-Pad119)") (class "Default")
      (node (ref "XDS1") (pin "119") (pinfunction "PP1_119") (pintype "bidirectional"))
    )
    (net (code "99") (name "unconnected-(XDS1B-PP2-Pad103)") (class "Default")
      (node (ref "XDS1") (pin "103") (pinfunction "PP2_103") (pintype "bidirectional"))
    )
    (net (code "100") (name "unconnected-(XDS1B-PP3-Pad104)") (class "Default")
      (node (ref "XDS1") (pin "104") (pinfunction "PP3_104") (pintype "bidirectional"))
    )
    (net (code "101") (name "unconnected-(XDS1B-PP4-Pad105)") (class "Default")
      (node (ref "XDS1") (pin "105") (pinfunction "PP4_105") (pintype "bidirectional"))
    )
    (net (code "102") (name "unconnected-(XDS1B-PP5-Pad106)") (class "Default")
      (node (ref "XDS1") (pin "106") (pinfunction "PP5_106") (pintype "bidirectional"))
    )
    (net (code "103") (name "unconnected-(XDS1B-PQ4-Pad102)") (class "Default")
      (node (ref "XDS1") (pin "102") (pinfunction "PQ4_102") (pintype "bidirectional"))
    )
    (net (code "104") (name "unconnected-(XDS1C-EN0RXIN-Pad53)") (class "Default")
      (node (ref "XDS1") (pin "53") (pinfunction "EN0RXIN_53") (pintype "bidirectional"))
    )
    (net (code "105") (name "unconnected-(XDS1C-EN0RXIP-Pad54)") (class "Default")
      (node (ref "XDS1") (pin "54") (pinfunction "EN0RXIP_54") (pintype "bidirectional"))
    )
    (net (code "106") (name "unconnected-(XDS1C-EN0TXON-Pad56)") (class "Default")
      (node (ref "XDS1") (pin "56") (pinfunction "EN0TXON_56") (pintype "bidirectional"))
    )
    (net (code "107") (name "unconnected-(XDS1C-EN0TXOP-Pad57)") (class "Default")
      (node (ref "XDS1") (pin "57") (pinfunction "EN0TXOP_57") (pintype "bidirectional"))
    )
    (net (code "108") (name "unconnected-(XDS1C-HIB-Pad65)") (class "Default")
      (node (ref "XDS1") (pin "65") (pinfunction "HIB_65") (pintype "output"))
    )
    (net (code "109") (name "unconnected-(XDS1C-XOSC1-Pad67)") (class "Default")
      (node (ref "XDS1") (pin "67") (pinfunction "XOSC1_67") (pintype "output"))
    )
  )
)
